# sh_stepper.net
KiCad netlist of a schematic drawn in Altium Designer
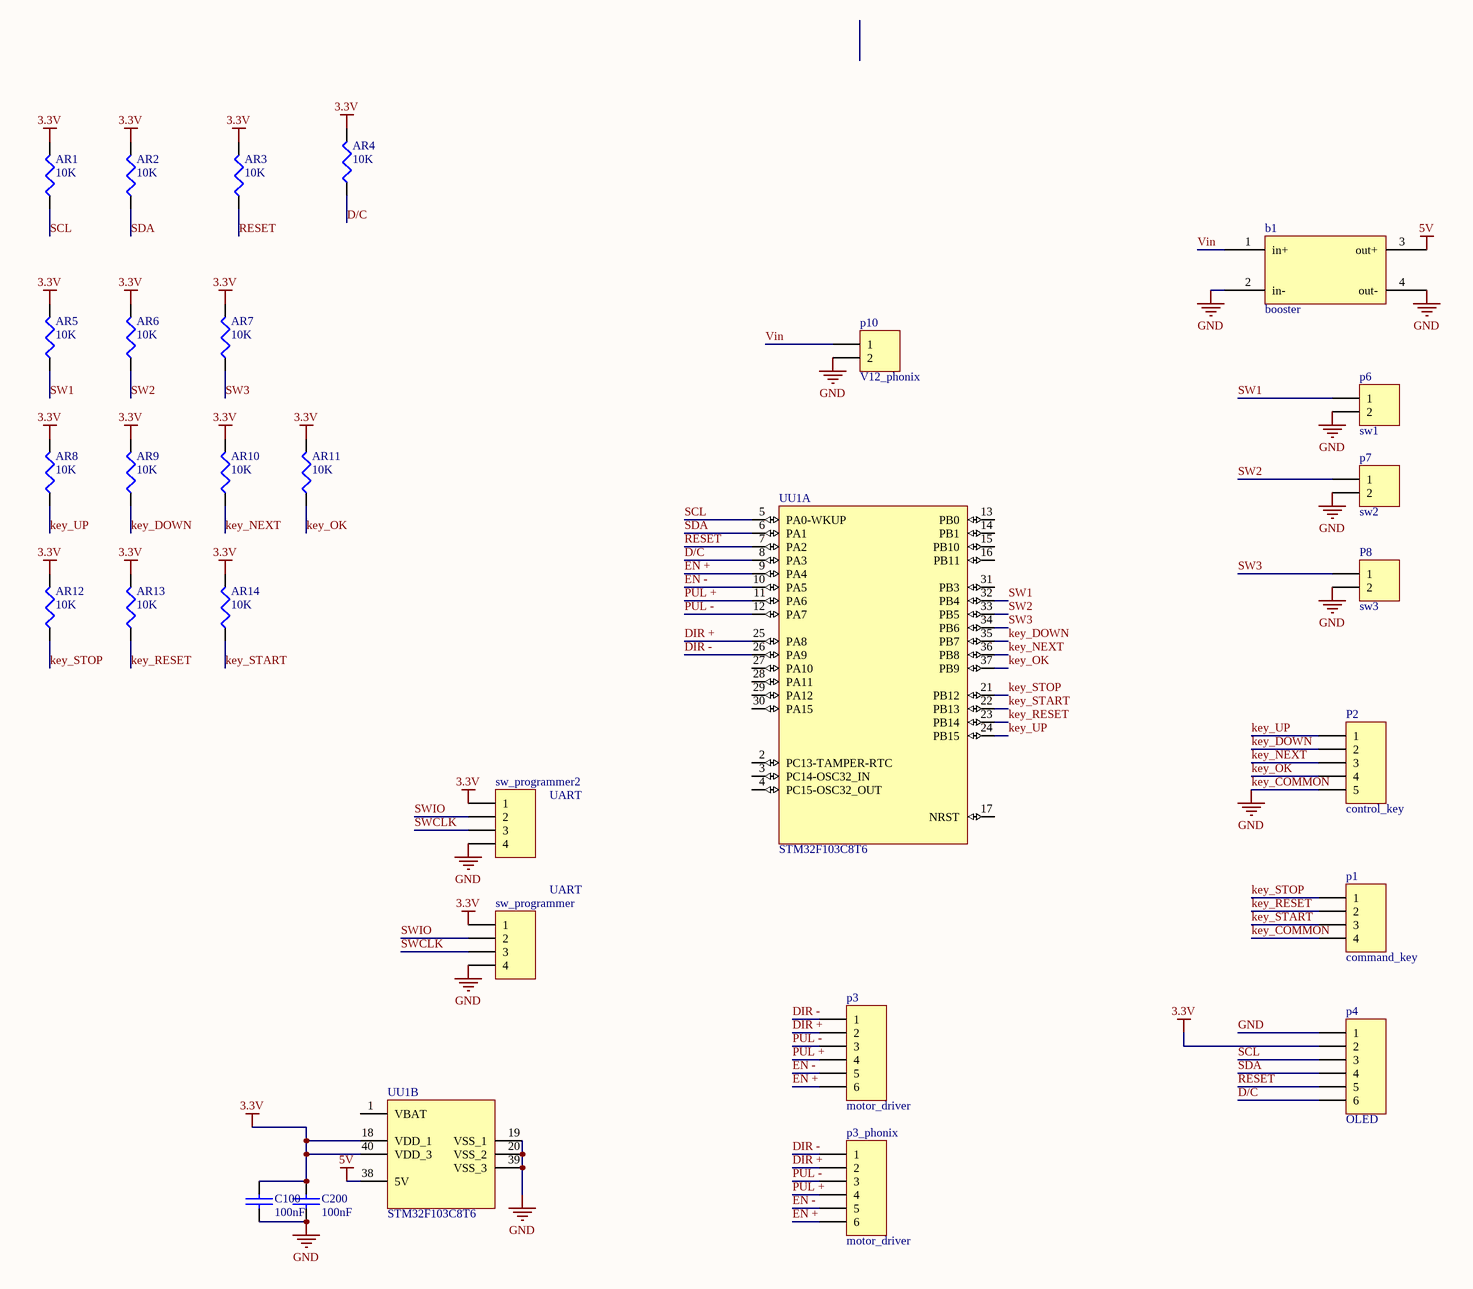
[diagram p0: sh_stepper.SchDoc]

(export (version "E")
  (design (tool "Eeschema 10.0.6"))
  (components
    (comp (ref "AR1")
      (value "10K")
      (footprint "c1206")
      (description "Resistor")
      (fields (field (name "Comment") "Res3") (field (name "PUBLISHER") "Altium Limited"))
      (libsource (lib "Calcul8") (part "Res3"))
    )
    (comp (ref "AR2")
      (value "10K")
      (footprint "c1206")
      (description "Resistor")
      (fields (field (name "Comment") "Res3") (field (name "PUBLISHER") "Altium Limited"))
      (libsource (lib "Calcul8") (part "Res3"))
    )
    (comp (ref "AR3")
      (value "10K")
      (footprint "c1206")
      (description "Resistor")
      (fields (field (name "Comment") "Res3") (field (name "PUBLISHER") "Altium Limited"))
      (libsource (lib "Calcul8") (part "Res3"))
    )
    (comp (ref "AR4")
      (value "10K")
      (footprint "c1206")
      (description "Resistor")
      (fields (field (name "Comment") "Res3") (field (name "PUBLISHER") "Altium Limited"))
      (libsource (lib "Calcul8") (part "Res3"))
    )
    (comp (ref "AR5")
      (value "10K")
      (footprint "c1206")
      (description "Resistor")
      (fields (field (name "Comment") "Res3") (field (name "PUBLISHER") "Altium Limited"))
      (libsource (lib "Calcul8") (part "Res3"))
    )
    (comp (ref "AR6")
      (value "10K")
      (footprint "c1206")
      (description "Resistor")
      (fields (field (name "Comment") "Res3") (field (name "PUBLISHER") "Altium Limited"))
      (libsource (lib "Calcul8") (part "Res3"))
    )
    (comp (ref "AR7")
      (value "10K")
      (footprint "c1206")
      (description "Resistor")
      (fields (field (name "Comment") "Res3") (field (name "PUBLISHER") "Altium Limited"))
      (libsource (lib "Calcul8") (part "Res3"))
    )
    (comp (ref "AR8")
      (value "10K")
      (footprint "c1206")
      (description "Resistor")
      (fields (field (name "Comment") "Res3") (field (name "PUBLISHER") "Altium Limited"))
      (libsource (lib "Calcul8") (part "Res3"))
    )
    (comp (ref "AR9")
      (value "10K")
      (footprint "c1206")
      (description "Resistor")
      (fields (field (name "Comment") "Res3") (field (name "PUBLISHER") "Altium Limited"))
      (libsource (lib "Calcul8") (part "Res3"))
    )
    (comp (ref "AR10")
      (value "10K")
      (footprint "c1206")
      (description "Resistor")
      (fields (field (name "Comment") "Res3") (field (name "PUBLISHER") "Altium Limited"))
      (libsource (lib "Calcul8") (part "Res3"))
    )
    (comp (ref "AR11")
      (value "10K")
      (footprint "c1206")
      (description "Resistor")
      (fields (field (name "Comment") "Res3") (field (name "PUBLISHER") "Altium Limited"))
      (libsource (lib "Calcul8") (part "Res3"))
    )
    (comp (ref "AR12")
      (value "10K")
      (footprint "c1206")
      (description "Resistor")
      (fields (field (name "Comment") "Res3") (field (name "PUBLISHER") "Altium Limited"))
      (libsource (lib "Calcul8") (part "Res3"))
    )
    (comp (ref "AR13")
      (value "10K")
      (footprint "c1206")
      (description "Resistor")
      (fields (field (name "Comment") "Res3") (field (name "PUBLISHER") "Altium Limited"))
      (libsource (lib "Calcul8") (part "Res3"))
    )
    (comp (ref "AR14")
      (value "10K")
      (footprint "c1206")
      (description "Resistor")
      (fields (field (name "Comment") "Res3") (field (name "PUBLISHER") "Altium Limited"))
      (libsource (lib "Calcul8") (part "Res3"))
    )
    (comp (ref "b1") (value "booster") (footprint "booster") (libsource (lib "Schlib1") (part "booster")))
    (comp (ref "C100")
      (value "100nF")
      (footprint "1206")
      (description "Bipolar Capacitor")
      (fields (field (name "VOLTAGE") "100V") (field (name "DESIGNER") "Saeid Jorablo"))
      (libsource (lib "My Library") (part "Cap-Bipolar"))
    )
    (comp (ref "C200")
      (value "100nF")
      (footprint "1206")
      (description "Bipolar Capacitor")
      (fields (field (name "VOLTAGE") "100V") (field (name "DESIGNER") "Saeid Jorablo"))
      (libsource (lib "My Library") (part "Cap-Bipolar"))
    )
    (comp (ref "p1")
      (value "command_key")
      (footprint "HDR1X4")
      (description "Header, 4-Pin")
      (fields (field (name "PUBLISHER") "Altium Limited"))
      (libsource (lib "Calcul8") (part "Header 4"))
    )
    (comp (ref "P2")
      (value "control_key")
      (footprint "HDR1X5")
      (description "Header, 5-Pin")
      (fields (field (name "PUBLISHER") "Altium Limited"))
      (libsource (lib "Miscellaneous Connectors") (part "Header 5"))
    )
    (comp (ref "p3")
      (value "motor_driver")
      (footprint "HDR1X6")
      (description "Header, 6-Pin")
      (fields (field (name "PUBLISHER") "Altium Limited"))
      (libsource (lib "Miscellaneous Connectors") (part "Header 6"))
    )
    (comp (ref "p3_phonix")
      (value "motor_driver")
      (footprint "phonix6")
      (description "Header, 6-Pin")
      (fields (field (name "PUBLISHER") "Altium Limited"))
      (libsource (lib "Miscellaneous Connectors") (part "Header 6"))
    )
    (comp (ref "p4")
      (value "OLED")
      (footprint "HDR1X6")
      (description "Header, 6-Pin")
      (fields (field (name "PUBLISHER") "Altium Limited"))
      (libsource (lib "Miscellaneous Connectors") (part "Header 6"))
    )
    (comp (ref "p6")
      (value "sw1")
      (footprint "HDR1X2")
      (description "Header, 2-Pin")
      (fields (field (name "PUBLISHER") "Altium Limited"))
      (libsource (lib "Miscellaneous Connectors") (part "Header 2"))
    )
    (comp (ref "p7")
      (value "sw2")
      (footprint "HDR1X2")
      (description "Header, 2-Pin")
      (fields (field (name "PUBLISHER") "Altium Limited"))
      (libsource (lib "Miscellaneous Connectors") (part "Header 2"))
    )
    (comp (ref "P8")
      (value "sw3")
      (footprint "HDR1X2")
      (description "Header, 2-Pin")
      (fields (field (name "PUBLISHER") "Altium Limited"))
      (libsource (lib "Miscellaneous Connectors") (part "Header 2"))
    )
    (comp (ref "p10")
      (value "V12_phonix")
      (footprint "phoenix terminal R 2")
      (description "Header, 2-Pin")
      (fields (field (name "PUBLISHER") "Altium Limited"))
      (libsource (lib "Miscellaneous Connectors") (part "Header 2"))
    )
    (comp (ref "sw_programmer")
      (value "~")
      (footprint "HDR1X4")
      (description "Header, 4-Pin")
      (fields (field (name "PUBLISHER") "Altium Limited"))
      (libsource (lib "Calcul8") (part "Header 4"))
    )
    (comp (ref "sw_programmer2")
      (value "~")
      (footprint "HDR1X4")
      (description "Header, 4-Pin")
      (fields (field (name "PUBLISHER") "Altium Limited"))
      (libsource (lib "Calcul8") (part "Header 4"))
    )
    (comp (ref "UU1")
      (value "STM32F103C8T6")
      (footprint "header_board_st_40")
      (libsource (lib "Schlib1") (part "STM32F103C8T6"))
    )
  )
  (nets
    (net (code "1") (name "/DIR +") (class "Default")
      (node (ref "UU1") (pin "25") (pinfunction "PA8_25") (pintype "bidirectional"))
      (node (ref "p3") (pin "2") (pinfunction "2_2") (pintype "passive"))
      (node (ref "p3_phonix") (pin "2") (pinfunction "2_2") (pintype "passive"))
    )
    (net (code "2") (name "/DIR -") (class "Default")
      (node (ref "UU1") (pin "26") (pinfunction "PA9_26") (pintype "bidirectional"))
      (node (ref "p3") (pin "1") (pinfunction "1_1") (pintype "passive"))
      (node (ref "p3_phonix") (pin "1") (pinfunction "1_1") (pintype "passive"))
    )
    (net (code "3") (name "/D{slash}C") (class "Default")
      (node (ref "AR4") (pin "1") (pinfunction "1_1") (pintype "passive"))
      (node (ref "UU1") (pin "8") (pinfunction "PA3_8") (pintype "bidirectional"))
      (node (ref "p4") (pin "6") (pinfunction "6_6") (pintype "passive"))
    )
    (net (code "4") (name "/EN +") (class "Default")
      (node (ref "UU1") (pin "9") (pinfunction "PA4_9") (pintype "bidirectional"))
      (node (ref "p3") (pin "6") (pinfunction "6_6") (pintype "passive"))
      (node (ref "p3_phonix") (pin "6") (pinfunction "6_6") (pintype "passive"))
    )
    (net (code "5") (name "/EN -") (class "Default")
      (node (ref "UU1") (pin "10") (pinfunction "PA5_10") (pintype "bidirectional"))
      (node (ref "p3") (pin "5") (pinfunction "5_5") (pintype "passive"))
      (node (ref "p3_phonix") (pin "5") (pinfunction "5_5") (pintype "passive"))
    )
    (net (code "6") (name "/PUL +") (class "Default")
      (node (ref "UU1") (pin "11") (pinfunction "PA6_11") (pintype "bidirectional"))
      (node (ref "p3") (pin "4") (pinfunction "4_4") (pintype "passive"))
      (node (ref "p3_phonix") (pin "4") (pinfunction "4_4") (pintype "passive"))
    )
    (net (code "7") (name "/PUL -") (class "Default")
      (node (ref "UU1") (pin "12") (pinfunction "PA7_12") (pintype "bidirectional"))
      (node (ref "p3") (pin "3") (pinfunction "3_3") (pintype "passive"))
      (node (ref "p3_phonix") (pin "3") (pinfunction "3_3") (pintype "passive"))
    )
    (net (code "8") (name "/RESET") (class "Default")
      (node (ref "AR3") (pin "1") (pinfunction "1_1") (pintype "passive"))
      (node (ref "UU1") (pin "7") (pinfunction "PA2_7") (pintype "bidirectional"))
      (node (ref "p4") (pin "5") (pinfunction "5_5") (pintype "passive"))
    )
    (net (code "9") (name "/SCL") (class "Default")
      (node (ref "AR1") (pin "1") (pinfunction "1_1") (pintype "passive"))
      (node (ref "UU1") (pin "5") (pinfunction "PA0-WKUP_5") (pintype "bidirectional"))
      (node (ref "p4") (pin "3") (pinfunction "3_3") (pintype "passive"))
    )
    (net (code "10") (name "/SDA") (class "Default")
      (node (ref "AR2") (pin "1") (pinfunction "1_1") (pintype "passive"))
      (node (ref "UU1") (pin "6") (pinfunction "PA1_6") (pintype "bidirectional"))
      (node (ref "p4") (pin "4") (pinfunction "4_4") (pintype "passive"))
    )
    (net (code "11") (name "/SW1") (class "Default")
      (node (ref "AR5") (pin "1") (pinfunction "1_1") (pintype "passive"))
      (node (ref "UU1") (pin "32") (pinfunction "PB4_32") (pintype "bidirectional"))
      (node (ref "p6") (pin "1") (pinfunction "1_1") (pintype "passive"))
    )
    (net (code "12") (name "/SW2") (class "Default")
      (node (ref "AR6") (pin "1") (pinfunction "1_1") (pintype "passive"))
      (node (ref "UU1") (pin "33") (pinfunction "PB5_33") (pintype "bidirectional"))
      (node (ref "p7") (pin "1") (pinfunction "1_1") (pintype "passive"))
    )
    (net (code "13") (name "/SW3") (class "Default")
      (node (ref "AR7") (pin "1") (pinfunction "1_1") (pintype "passive"))
      (node (ref "P8") (pin "1") (pinfunction "1_1") (pintype "passive"))
      (node (ref "UU1") (pin "34") (pinfunction "PB6_34") (pintype "bidirectional"))
    )
    (net (code "14") (name "/SWCLK") (class "Default")
      (node (ref "sw_programmer") (pin "3") (pinfunction "3_3") (pintype "passive"))
      (node (ref "sw_programmer2") (pin "3") (pinfunction "3_3") (pintype "passive"))
    )
    (net (code "15") (name "/SWIO") (class "Default")
      (node (ref "sw_programmer") (pin "2") (pinfunction "2_2") (pintype "passive"))
      (node (ref "sw_programmer2") (pin "2") (pinfunction "2_2") (pintype "passive"))
    )
    (net (code "16") (name "/Vin") (class "Default")
      (node (ref "b1") (pin "1") (pinfunction "in+_1") (pintype "passive"))
      (node (ref "p10") (pin "1") (pinfunction "1_1") (pintype "passive"))
    )
    (net (code "17") (name "/key_DOWN") (class "Default")
      (node (ref "AR9") (pin "1") (pinfunction "1_1") (pintype "passive"))
      (node (ref "P2") (pin "2") (pinfunction "2_2") (pintype "passive"))
      (node (ref "UU1") (pin "35") (pinfunction "PB7_35") (pintype "bidirectional"))
    )
    (net (code "18") (name "/key_NEXT") (class "Default")
      (node (ref "AR10") (pin "1") (pinfunction "1_1") (pintype "passive"))
      (node (ref "P2") (pin "3") (pinfunction "3_3") (pintype "passive"))
      (node (ref "UU1") (pin "36") (pinfunction "PB8_36") (pintype "bidirectional"))
    )
    (net (code "19") (name "/key_OK") (class "Default")
      (node (ref "AR11") (pin "1") (pinfunction "1_1") (pintype "passive"))
      (node (ref "P2") (pin "4") (pinfunction "4_4") (pintype "passive"))
      (node (ref "UU1") (pin "37") (pinfunction "PB9_37") (pintype "bidirectional"))
    )
    (net (code "20") (name "/key_RESET") (class "Default")
      (node (ref "AR13") (pin "1") (pinfunction "1_1") (pintype "passive"))
      (node (ref "UU1") (pin "23") (pinfunction "PB14_23") (pintype "bidirectional"))
      (node (ref "p1") (pin "2") (pinfunction "2_2") (pintype "passive"))
    )
    (net (code "21") (name "/key_START") (class "Default")
      (node (ref "AR14") (pin "1") (pinfunction "1_1") (pintype "passive"))
      (node (ref "UU1") (pin "22") (pinfunction "PB13_22") (pintype "bidirectional"))
      (node (ref "p1") (pin "3") (pinfunction "3_3") (pintype "passive"))
    )
    (net (code "22") (name "/key_STOP") (class "Default")
      (node (ref "AR12") (pin "1") (pinfunction "1_1") (pintype "passive"))
      (node (ref "UU1") (pin "21") (pinfunction "PB12_21") (pintype "bidirectional"))
      (node (ref "p1") (pin "1") (pinfunction "1_1") (pintype "passive"))
    )
    (net (code "23") (name "/key_UP") (class "Default")
      (node (ref "AR8") (pin "1") (pinfunction "1_1") (pintype "passive"))
      (node (ref "P2") (pin "1") (pinfunction "1_1") (pintype "passive"))
      (node (ref "UU1") (pin "24") (pinfunction "PB15_24") (pintype "bidirectional"))
    )
    (net (code "24") (name "3.3V") (class "Default")
      (node (ref "AR1") (pin "2") (pinfunction "2_2") (pintype "passive"))
      (node (ref "AR10") (pin "2") (pinfunction "2_2") (pintype "passive"))
      (node (ref "AR11") (pin "2") (pinfunction "2_2") (pintype "passive"))
      (node (ref "AR12") (pin "2") (pinfunction "2_2") (pintype "passive"))
      (node (ref "AR13") (pin "2") (pinfunction "2_2") (pintype "passive"))
      (node (ref "AR14") (pin "2") (pinfunction "2_2") (pintype "passive"))
      (node (ref "AR2") (pin "2") (pinfunction "2_2") (pintype "passive"))
      (node (ref "AR3") (pin "2") (pinfunction "2_2") (pintype "passive"))
      (node (ref "AR4") (pin "2") (pinfunction "2_2") (pintype "passive"))
      (node (ref "AR5") (pin "2") (pinfunction "2_2") (pintype "passive"))
      (node (ref "AR6") (pin "2") (pinfunction "2_2") (pintype "passive"))
      (node (ref "AR7") (pin "2") (pinfunction "2_2") (pintype "passive"))
      (node (ref "AR8") (pin "2") (pinfunction "2_2") (pintype "passive"))
      (node (ref "AR9") (pin "2") (pinfunction "2_2") (pintype "passive"))
      (node (ref "C100") (pin "1") (pinfunction "+_1") (pintype "passive"))
      (node (ref "C200") (pin "1") (pinfunction "+_1") (pintype "passive"))
      (node (ref "UU1") (pin "18") (pinfunction "VDD_1_18") (pintype "power_in"))
      (node (ref "UU1") (pin "40") (pinfunction "VDD_3_40") (pintype "power_in"))
      (node (ref "p4") (pin "2") (pinfunction "2_2") (pintype "passive"))
      (node (ref "sw_programmer") (pin "1") (pinfunction "1_1") (pintype "passive"))
      (node (ref "sw_programmer2") (pin "1") (pinfunction "1_1") (pintype "passive"))
    )
    (net (code "25") (name "5V") (class "Default")
      (node (ref "UU1") (pin "38") (pinfunction "5V_38") (pintype "power_in"))
      (node (ref "b1") (pin "3") (pinfunction "out+_3") (pintype "passive"))
    )
    (net (code "26") (name "GND") (class "Default")
      (node (ref "C100") (pin "2") (pinfunction "-_2") (pintype "passive"))
      (node (ref "C200") (pin "2") (pinfunction "-_2") (pintype "passive"))
      (node (ref "P2") (pin "5") (pinfunction "5_5") (pintype "passive"))
      (node (ref "P8") (pin "2") (pinfunction "2_2") (pintype "passive"))
      (node (ref "UU1") (pin "19") (pinfunction "VSS_1_19") (pintype "power_in"))
      (node (ref "UU1") (pin "20") (pinfunction "VSS_2_20") (pintype "power_in"))
      (node (ref "UU1") (pin "39") (pinfunction "VSS_3_39") (pintype "power_in"))
      (node (ref "b1") (pin "2") (pinfunction "in-_2") (pintype "passive"))
      (node (ref "b1") (pin "4") (pinfunction "out-_4") (pintype "passive"))
      (node (ref "p1") (pin "4") (pinfunction "4_4") (pintype "passive"))
      (node (ref "p10") (pin "2") (pinfunction "2_2") (pintype "passive"))
      (node (ref "p4") (pin "1") (pinfunction "1_1") (pintype "passive"))
      (node (ref "p6") (pin "2") (pinfunction "2_2") (pintype "passive"))
      (node (ref "p7") (pin "2") (pinfunction "2_2") (pintype "passive"))
      (node (ref "sw_programmer") (pin "4") (pinfunction "4_4") (pintype "passive"))
      (node (ref "sw_programmer2") (pin "4") (pinfunction "4_4") (pintype "passive"))
    )
    (net (code "27") (name "unconnected-(UU1A-NRST-Pad17)") (class "Default")
      (node (ref "UU1") (pin "17") (pinfunction "NRST_17") (pintype "bidirectional"))
    )
    (net (code "28") (name "unconnected-(UU1A-PA10-Pad27)") (class "Default")
      (node (ref "UU1") (pin "27") (pinfunction "PA10_27") (pintype "bidirectional"))
    )
    (net (code "29") (name "unconnected-(UU1A-PA11-Pad28)") (class "Default")
      (node (ref "UU1") (pin "28") (pinfunction "PA11_28") (pintype "bidirectional"))
    )
    (net (code "30") (name "unconnected-(UU1A-PA12-Pad29)") (class "Default")
      (node (ref "UU1") (pin "29") (pinfunction "PA12_29") (pintype "bidirectional"))
    )
    (net (code "31") (name "unconnected-(UU1A-PA15-Pad30)") (class "Default")
      (node (ref "UU1") (pin "30") (pinfunction "PA15_30") (pintype "bidirectional"))
    )
    (net (code "32") (name "unconnected-(UU1A-PB0-Pad13)") (class "Default")
      (node (ref "UU1") (pin "13") (pinfunction "PB0_13") (pintype "bidirectional"))
    )
    (net (code "33") (name "unconnected-(UU1A-PB1-Pad14)") (class "Default")
      (node (ref "UU1") (pin "14") (pinfunction "PB1_14") (pintype "bidirectional"))
    )
    (net (code "34") (name "unconnected-(UU1A-PB3-Pad31)") (class "Default")
      (node (ref "UU1") (pin "31") (pinfunction "PB3_31") (pintype "bidirectional"))
    )
    (net (code "35") (name "unconnected-(UU1A-PB10-Pad15)") (class "Default")
      (node (ref "UU1") (pin "15") (pinfunction "PB10_15") (pintype "bidirectional"))
    )
    (net (code "36") (name "unconnected-(UU1A-PB11-Pad16)") (class "Default")
      (node (ref "UU1") (pin "16") (pinfunction "PB11_16") (pintype "bidirectional"))
    )
    (net (code "37") (name "unconnected-(UU1A-PC13-TAMPER-RTC-Pad2)") (class "Default")
      (node (ref "UU1") (pin "2") (pinfunction "PC13-TAMPER-RTC_2") (pintype "bidirectional"))
    )
    (net (code "38") (name "unconnected-(UU1A-PC14-OSC32_IN-Pad3)") (class "Default")
      (node (ref "UU1") (pin "3") (pinfunction "PC14-OSC32_IN_3") (pintype "bidirectional"))
    )
    (net (code "39") (name "unconnected-(UU1A-PC15-OSC32_OUT-Pad4)") (class "Default")
      (node (ref "UU1") (pin "4") (pinfunction "PC15-OSC32_OUT_4") (pintype "bidirectional"))
    )
    (net (code "40") (name "unconnected-(UU1B-VBAT-Pad1)") (class "Default")
      (node (ref "UU1") (pin "1") (pinfunction "VBAT_1") (pintype "power_in"))
    )
  )
)
